# Sheet1.net
KiCad netlist of a schematic drawn in Altium Designer
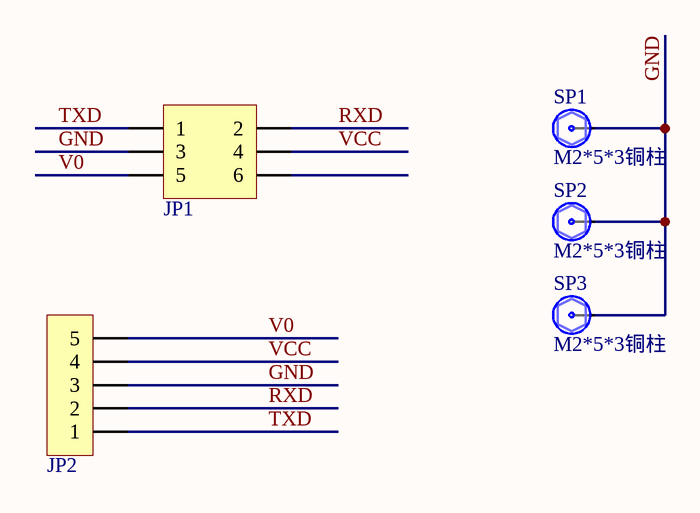
[diagram p0: Sheet1.SchDoc]

(export (version "E")
  (design (tool "Eeschema 10.0.6"))
  (components
    (comp (ref "JP1")
      (value "Header3X2")
      (footprint "HX25080-Y-A-PT")
      (description "3*2P接插件")
      (libsource (lib "18 - 接插件-脚距2.54mm (100mil) ") (part "Header 3X2"))
    )
    (comp (ref "JP2")
      (value "HDR-1X5")
      (footprint "JXM-H2")
      (description "5P接插件")
      (libsource (lib "18 - 接插件-脚距2.54mm (100mil) ") (part "Header 5"))
    )
    (comp (ref "SP1")
      (value "M2*5*3铜柱")
      (footprint "M2*5*3")
      (description "铜柱")
      (libsource (lib "10 - 未分类元器件") (part "铜柱小焊盘"))
    )
    (comp (ref "SP2")
      (value "M2*5*3铜柱")
      (footprint "M2*5*3")
      (description "铜柱")
      (libsource (lib "10 - 未分类元器件") (part "铜柱小焊盘"))
    )
    (comp (ref "SP3")
      (value "M2*5*3铜柱")
      (footprint "M2*5*3")
      (description "铜柱")
      (libsource (lib "10 - 未分类元器件") (part "铜柱小焊盘"))
    )
  )
  (nets
    (net (code "1") (name "/GND") (class "Default")
      (node (ref "JP1") (pin "3") (pinfunction "3_3") (pintype "passive"))
      (node (ref "JP2") (pin "3") (pinfunction "3_3") (pintype "passive"))
      (node (ref "SP1") (pin "1") (pinfunction "1_1") (pintype "passive"))
      (node (ref "SP2") (pin "1") (pinfunction "1_1") (pintype "passive"))
      (node (ref "SP3") (pin "1") (pinfunction "1_1") (pintype "passive"))
    )
    (net (code "2") (name "/RXD") (class "Default")
      (node (ref "JP1") (pin "2") (pinfunction "2_2") (pintype "passive"))
      (node (ref "JP2") (pin "2") (pinfunction "2_2") (pintype "passive"))
    )
    (net (code "3") (name "/TXD") (class "Default")
      (node (ref "JP1") (pin "1") (pinfunction "1_1") (pintype "passive"))
      (node (ref "JP2") (pin "1") (pinfunction "1_1") (pintype "passive"))
    )
    (net (code "4") (name "/V0") (class "Default")
      (node (ref "JP1") (pin "5") (pinfunction "5_5") (pintype "passive"))
      (node (ref "JP2") (pin "5") (pinfunction "5_5") (pintype "passive"))
    )
    (net (code "5") (name "/VCC") (class "Default")
      (node (ref "JP1") (pin "4") (pinfunction "4_4") (pintype "passive"))
      (node (ref "JP2") (pin "4") (pinfunction "4_4") (pintype "passive"))
    )
    (net (code "6") (name "unconnected-(JP1-Pad6)") (class "Default")
      (node (ref "JP1") (pin "6") (pinfunction "6_6") (pintype "passive"))
    )
  )
)
